# joystick.net
KiCad netlist of a schematic drawn in Altium Designer
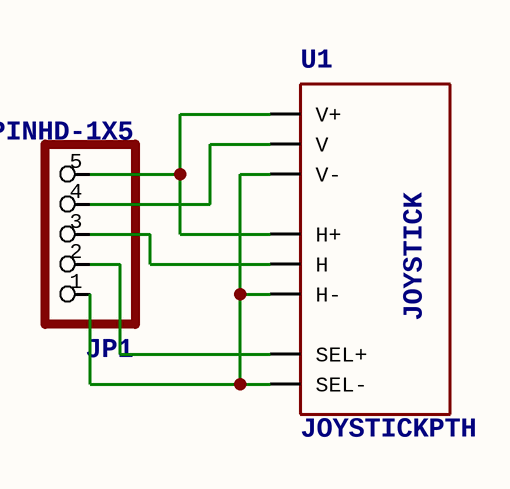
[diagram p0: joystick.SchDoc]

(export (version "E")
  (design (tool "Eeschema 10.0.6"))
  (components
    (comp (ref "JP1")
      (value "PINHD-1X5")
      (footprint "1X05")
      (description "<b>PIN HEADER</b>")
      (fields (field (name ">NAME") "JP1") (field (name ">VALUE") "PINHD-1X5"))
      (libsource (lib "pinhead") (part "PINHD-1X5"))
    )
    (comp (ref "U1")
      (value "JOYSTICKPTH")
      (footprint "JOYSTICK")
      (fields
        (field (name ">NAME") "U1")
        (field (name ">VALUE") "JOYSTICKPTH")
        (field (name "JOYSTICK") "JOYSTICK")
      )
      (libsource (lib "adafruit") (part "JOYSTICKPTH"))
    )
  )
  (nets
    (net (code "1") (name "Net-(U1-H)") (class "Default")
      (node (ref "JP1") (pin "3") (pinfunction "3_3") (pintype "passive"))
      (node (ref "U1") (pin "H2") (pinfunction "H_H2") (pintype "passive"))
    )
    (net (code "2") (name "Net-(U1-H+)") (class "Default")
      (node (ref "JP1") (pin "5") (pinfunction "5_5") (pintype "passive"))
      (node (ref "U1") (pin "H1") (pinfunction "H+_H1") (pintype "passive"))
      (node (ref "U1") (pin "V1") (pinfunction "V+_V1") (pintype "passive"))
    )
    (net (code "3") (name "Net-(U1-H-)") (class "Default")
      (node (ref "JP1") (pin "1") (pinfunction "1_1") (pintype "passive"))
      (node (ref "U1") (pin "B2A") (pinfunction "SEL-_B2A") (pintype "passive"))
      (node (ref "U1") (pin "H3") (pinfunction "H-_H3") (pintype "passive"))
      (node (ref "U1") (pin "V3") (pinfunction "V-_V3") (pintype "passive"))
    )
    (net (code "4") (name "Net-(U1-SEL+)") (class "Default")
      (node (ref "JP1") (pin "2") (pinfunction "2_2") (pintype "passive"))
      (node (ref "U1") (pin "B1A") (pinfunction "SEL+_B1A") (pintype "passive"))
    )
    (net (code "5") (name "Net-(U1-V)") (class "Default")
      (node (ref "JP1") (pin "4") (pinfunction "4_4") (pintype "passive"))
      (node (ref "U1") (pin "V2") (pinfunction "V_V2") (pintype "passive"))
    )
  )
)
